# Memory.net
KiCad netlist of a schematic drawn in Altium Designer
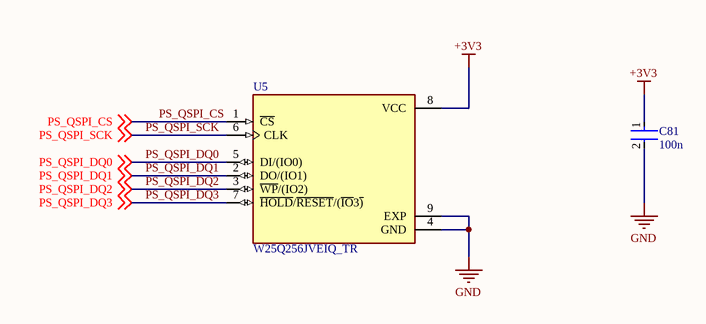
[diagram p0: Memory.SchDoc]

(export (version "E")
  (design (tool "Eeschema 10.0.6"))
  (components
    (comp (ref "C81")
      (value "100n")
      (footprint "FP-CC0603-DA-MFG")
      (description "CAP CER 0.1UF 50V X7R 0603")
      (fields (field (name "MANUFACTURER") "YAGEO") (field (name "VOLTAGE") "50 V"))
      (libsource (lib "Altium Content Vault") (part "11868f565c42a9108669ba33697ecf6"))
    )
    (comp (ref "U5")
      (value "W25Q256JVEIQ_TR")
      (footprint "SON127P600X800X80-9N")
      (description "FLASH - NOR Memory IC 256Mb (32M x 8) SPI - Quad I/O 133 MHz 8-WSON (8x6)")
      (fields (field (name "MP") "W25Q256JVEIQ TR") (field (name "MF") "Winbond"))
      (libsource (lib "W25Q256JVEIQ_TR") (part "W25Q256JVEIQ_TR"))
    )
  )
  (nets
    (net (code "1") (name "+3V3") (class "Default")
      (node (ref "C81") (pin "1") (pinfunction "1_1") (pintype "passive"))
      (node (ref "U5") (pin "8") (pinfunction "VCC_8") (pintype "power_in"))
    )
    (net (code "2") (name "GND") (class "Default")
      (node (ref "C81") (pin "2") (pinfunction "2_2") (pintype "passive"))
      (node (ref "U5") (pin "4") (pinfunction "GND_4") (pintype "power_in"))
      (node (ref "U5") (pin "9") (pinfunction "EXP_9") (pintype "passive"))
    )
    (net (code "3") (name "PS_QSPI_CS") (class "Default")
      (node (ref "U5") (pin "1") (pinfunction "~{CS}_1") (pintype "input"))
    )
    (net (code "4") (name "PS_QSPI_DQ0") (class "Default")
      (node (ref "U5") (pin "5") (pinfunction "DI/(IO0)_5") (pintype "bidirectional"))
    )
    (net (code "5") (name "PS_QSPI_DQ1") (class "Default")
      (node (ref "U5") (pin "2") (pinfunction "DO/(IO1)_2") (pintype "bidirectional"))
    )
    (net (code "6") (name "PS_QSPI_DQ2") (class "Default")
      (node (ref "U5") (pin "3") (pinfunction "~{WP}/(IO2)_3") (pintype "bidirectional"))
    )
    (net (code "7") (name "PS_QSPI_DQ3") (class "Default")
      (node (ref "U5") (pin "7") (pinfunction "~{HOLD}/~{RESET}/(~{IO}3~{)}_7") (pintype "bidirectional"))
    )
    (net (code "8") (name "PS_QSPI_SCK") (class "Default")
      (node (ref "U5") (pin "6") (pinfunction "CLK_6") (pintype "input"))
    )
  )
)
